# eeprom_emu_bt.net
KiCad netlist of a schematic drawn in EAGLE
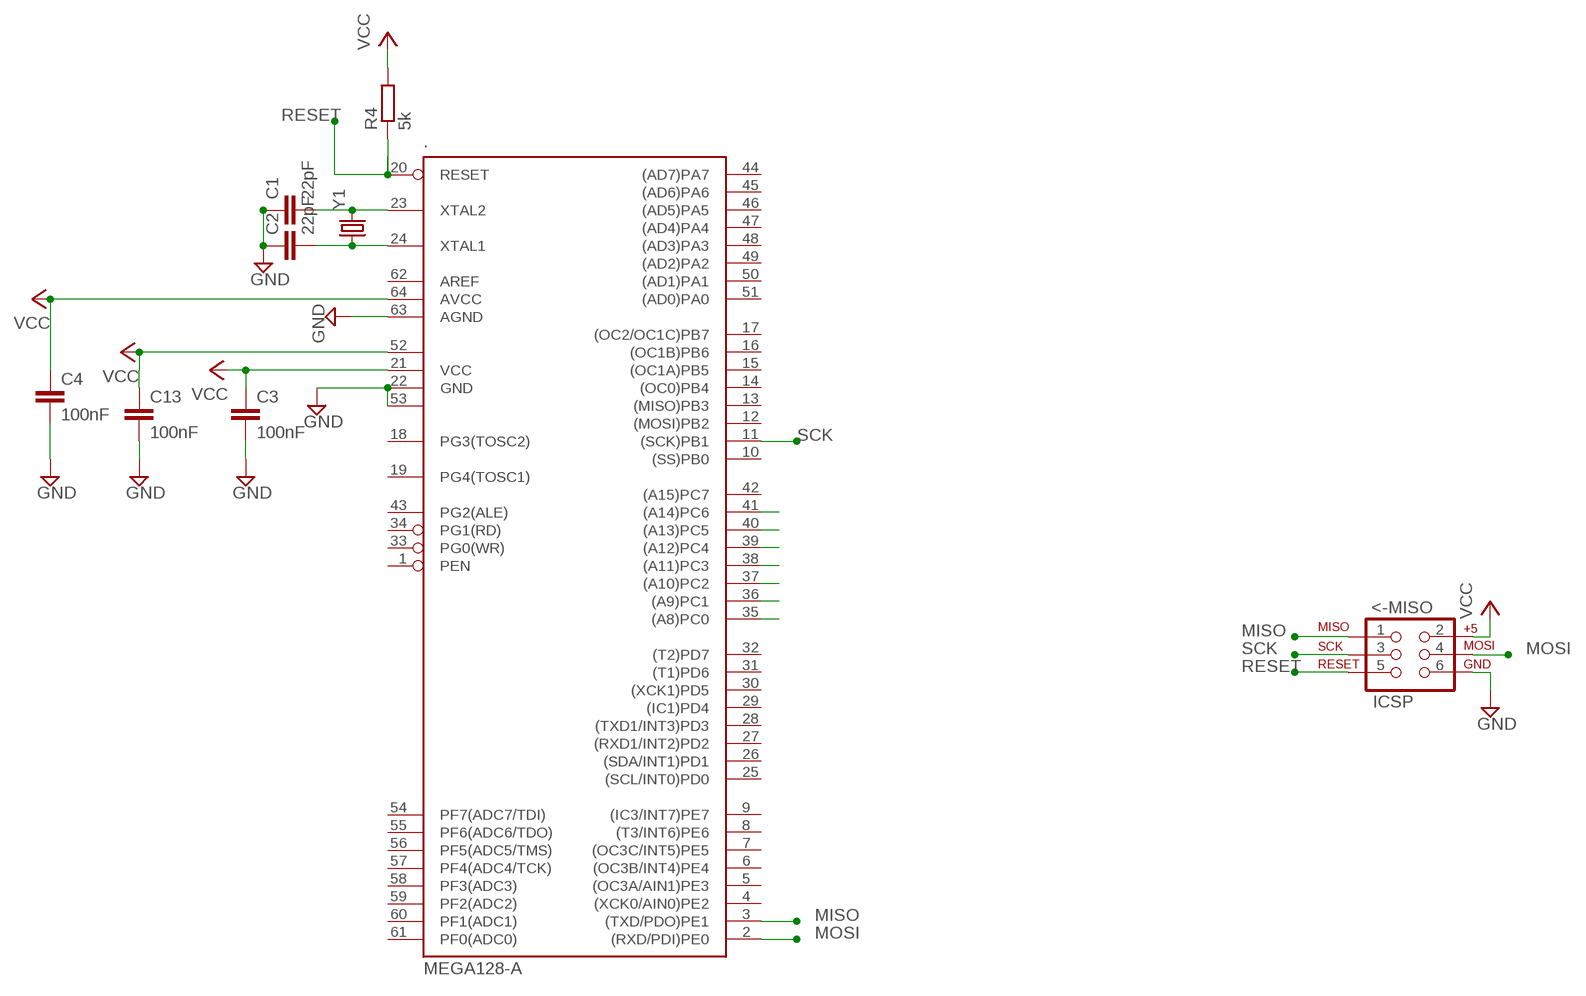
[diagram p0: schematic, sheet 1]

(export (version "E")
  (design (tool "Eeschema 10.0.6"))
  (components
    (comp (ref ".")
      (value "MEGA128-A")
      (footprint "eagle-import:TQFP64")
      (libsource (lib "eagle-import") (part "MEGA128-A"))
    )
    (comp (ref "<-MISO")
      (value "ICSP")
      (footprint "eagle-import:2X3")
      (libsource (lib "eagle-import") (part "AVR_SPI_PRG_6PTH"))
    )
    (comp (ref "C1")
      (value "22pF")
      (footprint "eagle-import:C0805")
      (libsource (lib "eagle-import") (part "C-EUC0805"))
    )
    (comp (ref "C2")
      (value "22pF")
      (footprint "eagle-import:C0805")
      (libsource (lib "eagle-import") (part "C-EUC0805"))
    )
    (comp (ref "C3")
      (value "100nF")
      (footprint "eagle-import:C0805")
      (libsource (lib "eagle-import") (part "C-EUC0805"))
    )
    (comp (ref "C4")
      (value "100nF")
      (footprint "eagle-import:C0805")
      (libsource (lib "eagle-import") (part "C-EUC0805"))
    )
    (comp (ref "C13")
      (value "100nF")
      (footprint "eagle-import:C0805")
      (libsource (lib "eagle-import") (part "C-EUC0805"))
    )
    (comp (ref "R4")
      (value "5k")
      (footprint "eagle-import:R0805")
      (libsource (lib "eagle-import") (part "R-EU_R0805"))
    )
    (comp (ref "Y1")
      (value "CRYSTALHC49US")
      (footprint "eagle-import:HC49US")
      (libsource (lib "eagle-import") (part "CRYSTALHC49US"))
    )
  )
  (nets
    (net (code "1") (name "/MISO") (class "Default")
      (node (ref ".") (pin "3") (pinfunction "(TXD/PDO)PE1_3") (pintype "bidirectional"))
      (node (ref "<-MISO") (pin "1") (pinfunction "1_1") (pintype "passive"))
    )
    (net (code "2") (name "/MOSI") (class "Default")
      (node (ref ".") (pin "2") (pinfunction "(RXD/PDI)PE0_2") (pintype "bidirectional"))
      (node (ref "<-MISO") (pin "4") (pinfunction "4_4") (pintype "passive"))
    )
    (net (code "3") (name "/RESET") (class "Default")
      (node (ref ".") (pin "20") (pinfunction "RESET_20") (pintype "input"))
      (node (ref "<-MISO") (pin "5") (pinfunction "5_5") (pintype "passive"))
      (node (ref "R4") (pin "1") (pinfunction "1_1") (pintype "passive"))
    )
    (net (code "4") (name "/SCK") (class "Default")
      (node (ref ".") (pin "11") (pinfunction "(SCK)PB1_11") (pintype "bidirectional"))
      (node (ref "<-MISO") (pin "3") (pinfunction "3_3") (pintype "passive"))
    )
    (net (code "5") (name "GND") (class "Default")
      (node (ref ".") (pin "22") (pinfunction "GND_22") (pintype "power_in"))
      (node (ref ".") (pin "53") (pinfunction "GND1_53") (pintype "power_in"))
      (node (ref ".") (pin "63") (pinfunction "AGND_63") (pintype "bidirectional"))
      (node (ref "<-MISO") (pin "6") (pinfunction "6_6") (pintype "passive"))
      (node (ref "C1") (pin "1") (pinfunction "1_1") (pintype "passive"))
      (node (ref "C13") (pin "2") (pinfunction "2_2") (pintype "passive"))
      (node (ref "C2") (pin "1") (pinfunction "1_1") (pintype "passive"))
      (node (ref "C3") (pin "2") (pinfunction "2_2") (pintype "passive"))
      (node (ref "C4") (pin "2") (pinfunction "2_2") (pintype "passive"))
    )
    (net (code "6") (name "Net-(.-XTAL1)") (class "Default")
      (node (ref ".") (pin "24") (pinfunction "XTAL1_24") (pintype "bidirectional"))
      (node (ref "C2") (pin "2") (pinfunction "2_2") (pintype "passive"))
      (node (ref "Y1") (pin "1") (pinfunction "1_1") (pintype "passive"))
    )
    (net (code "7") (name "Net-(.-XTAL2)") (class "Default")
      (node (ref ".") (pin "23") (pinfunction "XTAL2_23") (pintype "bidirectional"))
      (node (ref "C1") (pin "2") (pinfunction "2_2") (pintype "passive"))
      (node (ref "Y1") (pin "2") (pinfunction "2_2") (pintype "passive"))
    )
    (net (code "8") (name "VCC") (class "Default")
      (node (ref ".") (pin "21") (pinfunction "VCC_21") (pintype "power_in"))
      (node (ref ".") (pin "52") (pinfunction "VCC1_52") (pintype "power_in"))
      (node (ref ".") (pin "64") (pinfunction "AVCC_64") (pintype "bidirectional"))
      (node (ref "<-MISO") (pin "2") (pinfunction "2_2") (pintype "passive"))
      (node (ref "C13") (pin "1") (pinfunction "1_1") (pintype "passive"))
      (node (ref "C3") (pin "1") (pinfunction "1_1") (pintype "passive"))
      (node (ref "C4") (pin "1") (pinfunction "1_1") (pintype "passive"))
      (node (ref "R4") (pin "2") (pinfunction "2_2") (pintype "passive"))
    )
    (net (code "9") (name "unconnected-(.-(A8)PC0-Pad35)") (class "Default")
      (node (ref ".") (pin "35") (pinfunction "(A8)PC0_35") (pintype "output"))
    )
    (net (code "10") (name "unconnected-(.-(A9)PC1-Pad36)") (class "Default")
      (node (ref ".") (pin "36") (pinfunction "(A9)PC1_36") (pintype "output"))
    )
    (net (code "11") (name "unconnected-(.-(A10)PC2-Pad37)") (class "Default")
      (node (ref ".") (pin "37") (pinfunction "(A10)PC2_37") (pintype "output"))
    )
    (net (code "12") (name "unconnected-(.-(A11)PC3-Pad38)") (class "Default")
      (node (ref ".") (pin "38") (pinfunction "(A11)PC3_38") (pintype "output"))
    )
    (net (code "13") (name "unconnected-(.-(A12)PC4-Pad39)") (class "Default")
      (node (ref ".") (pin "39") (pinfunction "(A12)PC4_39") (pintype "output"))
    )
    (net (code "14") (name "unconnected-(.-(A13)PC5-Pad40)") (class "Default")
      (node (ref ".") (pin "40") (pinfunction "(A13)PC5_40") (pintype "output"))
    )
    (net (code "15") (name "unconnected-(.-(A14)PC6-Pad41)") (class "Default")
      (node (ref ".") (pin "41") (pinfunction "(A14)PC6_41") (pintype "output"))
    )
    (net (code "16") (name "unconnected-(.-(A15)PC7-Pad42)") (class "Default")
      (node (ref ".") (pin "42") (pinfunction "(A15)PC7_42") (pintype "output"))
    )
    (net (code "17") (name "unconnected-(.-(AD0)PA0-Pad51)") (class "Default")
      (node (ref ".") (pin "51") (pinfunction "(AD0)PA0_51") (pintype "bidirectional"))
    )
    (net (code "18") (name "unconnected-(.-(AD1)PA1-Pad50)") (class "Default")
      (node (ref ".") (pin "50") (pinfunction "(AD1)PA1_50") (pintype "bidirectional"))
    )
    (net (code "19") (name "unconnected-(.-(AD2)PA2-Pad49)") (class "Default")
      (node (ref ".") (pin "49") (pinfunction "(AD2)PA2_49") (pintype "bidirectional"))
    )
    (net (code "20") (name "unconnected-(.-(AD3)PA3-Pad48)") (class "Default")
      (node (ref ".") (pin "48") (pinfunction "(AD3)PA3_48") (pintype "bidirectional"))
    )
    (net (code "21") (name "unconnected-(.-(AD4)PA4-Pad47)") (class "Default")
      (node (ref ".") (pin "47") (pinfunction "(AD4)PA4_47") (pintype "bidirectional"))
    )
    (net (code "22") (name "unconnected-(.-(AD5)PA5-Pad46)") (class "Default")
      (node (ref ".") (pin "46") (pinfunction "(AD5)PA5_46") (pintype "bidirectional"))
    )
    (net (code "23") (name "unconnected-(.-(AD6)PA6-Pad45)") (class "Default")
      (node (ref ".") (pin "45") (pinfunction "(AD6)PA6_45") (pintype "bidirectional"))
    )
    (net (code "24") (name "unconnected-(.-(AD7)PA7-Pad44)") (class "Default")
      (node (ref ".") (pin "44") (pinfunction "(AD7)PA7_44") (pintype "bidirectional"))
    )
    (net (code "25") (name "unconnected-(.-(IC1)PD4-Pad29)") (class "Default")
      (node (ref ".") (pin "29") (pinfunction "(IC1)PD4_29") (pintype "bidirectional"))
    )
    (net (code "26") (name "unconnected-(.-(IC3{slash}INT7)PE7-Pad9)") (class "Default")
      (node (ref ".") (pin "9") (pinfunction "(IC3/INT7)PE7_9") (pintype "bidirectional"))
    )
    (net (code "27") (name "unconnected-(.-(MISO)PB3-Pad13)") (class "Default")
      (node (ref ".") (pin "13") (pinfunction "(MISO)PB3_13") (pintype "bidirectional"))
    )
    (net (code "28") (name "unconnected-(.-(MOSI)PB2-Pad12)") (class "Default")
      (node (ref ".") (pin "12") (pinfunction "(MOSI)PB2_12") (pintype "bidirectional"))
    )
    (net (code "29") (name "unconnected-(.-(OC0)PB4-Pad14)") (class "Default")
      (node (ref ".") (pin "14") (pinfunction "(OC0)PB4_14") (pintype "bidirectional"))
    )
    (net (code "30") (name "unconnected-(.-(OC1A)PB5-Pad15)") (class "Default")
      (node (ref ".") (pin "15") (pinfunction "(OC1A)PB5_15") (pintype "bidirectional"))
    )
    (net (code "31") (name "unconnected-(.-(OC1B)PB6-Pad16)") (class "Default")
      (node (ref ".") (pin "16") (pinfunction "(OC1B)PB6_16") (pintype "bidirectional"))
    )
    (net (code "32") (name "unconnected-(.-(OC2{slash}OC1C)PB7-Pad17)") (class "Default")
      (node (ref ".") (pin "17") (pinfunction "(OC2/OC1C)PB7_17") (pintype "bidirectional"))
    )
    (net (code "33") (name "unconnected-(.-(OC3A{slash}AIN1)PE3-Pad5)") (class "Default")
      (node (ref ".") (pin "5") (pinfunction "(OC3A/AIN1)PE3_5") (pintype "bidirectional"))
    )
    (net (code "34") (name "unconnected-(.-(OC3B{slash}INT4)PE4-Pad6)") (class "Default")
      (node (ref ".") (pin "6") (pinfunction "(OC3B/INT4)PE4_6") (pintype "bidirectional"))
    )
    (net (code "35") (name "unconnected-(.-(OC3C{slash}INT5)PE5-Pad7)") (class "Default")
      (node (ref ".") (pin "7") (pinfunction "(OC3C/INT5)PE5_7") (pintype "bidirectional"))
    )
    (net (code "36") (name "unconnected-(.-(RXD1{slash}INT2)PD2-Pad27)") (class "Default")
      (node (ref ".") (pin "27") (pinfunction "(RXD1/INT2)PD2_27") (pintype "bidirectional"))
    )
    (net (code "37") (name "unconnected-(.-(SCL{slash}INT0)PD0-Pad25)") (class "Default")
      (node (ref ".") (pin "25") (pinfunction "(SCL/INT0)PD0_25") (pintype "bidirectional"))
    )
    (net (code "38") (name "unconnected-(.-(SDA{slash}INT1)PD1-Pad26)") (class "Default")
      (node (ref ".") (pin "26") (pinfunction "(SDA/INT1)PD1_26") (pintype "bidirectional"))
    )
    (net (code "39") (name "unconnected-(.-(SS)PB0-Pad10)") (class "Default")
      (node (ref ".") (pin "10") (pinfunction "(SS)PB0_10") (pintype "bidirectional"))
    )
    (net (code "40") (name "unconnected-(.-(T1)PD6-Pad31)") (class "Default")
      (node (ref ".") (pin "31") (pinfunction "(T1)PD6_31") (pintype "bidirectional"))
    )
    (net (code "41") (name "unconnected-(.-(T2)PD7-Pad32)") (class "Default")
      (node (ref ".") (pin "32") (pinfunction "(T2)PD7_32") (pintype "bidirectional"))
    )
    (net (code "42") (name "unconnected-(.-(T3{slash}INT6)PE6-Pad8)") (class "Default")
      (node (ref ".") (pin "8") (pinfunction "(T3/INT6)PE6_8") (pintype "bidirectional"))
    )
    (net (code "43") (name "unconnected-(.-(TXD1{slash}INT3)PD3-Pad28)") (class "Default")
      (node (ref ".") (pin "28") (pinfunction "(TXD1/INT3)PD3_28") (pintype "bidirectional"))
    )
    (net (code "44") (name "unconnected-(.-(XCK0{slash}AIN0)PE2-Pad4)") (class "Default")
      (node (ref ".") (pin "4") (pinfunction "(XCK0/AIN0)PE2_4") (pintype "bidirectional"))
    )
    (net (code "45") (name "unconnected-(.-(XCK1)PD5-Pad30)") (class "Default")
      (node (ref ".") (pin "30") (pinfunction "(XCK1)PD5_30") (pintype "bidirectional"))
    )
    (net (code "46") (name "unconnected-(.-AREF-Pad62)") (class "Default")
      (node (ref ".") (pin "62") (pinfunction "AREF_62") (pintype "bidirectional"))
    )
    (net (code "47") (name "unconnected-(.-PEN-Pad1)") (class "Default")
      (node (ref ".") (pin "1") (pinfunction "PEN_1") (pintype "input"))
    )
    (net (code "48") (name "unconnected-(.-PF0(ADC0)-Pad61)") (class "Default")
      (node (ref ".") (pin "61") (pinfunction "PF0(ADC0)_61") (pintype "input"))
    )
    (net (code "49") (name "unconnected-(.-PF1(ADC1)-Pad60)") (class "Default")
      (node (ref ".") (pin "60") (pinfunction "PF1(ADC1)_60") (pintype "input"))
    )
    (net (code "50") (name "unconnected-(.-PF2(ADC2)-Pad59)") (class "Default")
      (node (ref ".") (pin "59") (pinfunction "PF2(ADC2)_59") (pintype "input"))
    )
    (net (code "51") (name "unconnected-(.-PF3(ADC3)-Pad58)") (class "Default")
      (node (ref ".") (pin "58") (pinfunction "PF3(ADC3)_58") (pintype "input"))
    )
    (net (code "52") (name "unconnected-(.-PF4(ADC4{slash}TCK)-Pad57)") (class "Default")
      (node (ref ".") (pin "57") (pinfunction "PF4(ADC4/TCK)_57") (pintype "input"))
    )
    (net (code "53") (name "unconnected-(.-PF5(ADC5{slash}TMS)-Pad56)") (class "Default")
      (node (ref ".") (pin "56") (pinfunction "PF5(ADC5/TMS)_56") (pintype "input"))
    )
    (net (code "54") (name "unconnected-(.-PF6(ADC6{slash}TDO)-Pad55)") (class "Default")
      (node (ref ".") (pin "55") (pinfunction "PF6(ADC6/TDO)_55") (pintype "input"))
    )
    (net (code "55") (name "unconnected-(.-PF7(ADC7{slash}TDI)-Pad54)") (class "Default")
      (node (ref ".") (pin "54") (pinfunction "PF7(ADC7/TDI)_54") (pintype "input"))
    )
    (net (code "56") (name "unconnected-(.-PG0(WR)-Pad33)") (class "Default")
      (node (ref ".") (pin "33") (pinfunction "PG0(WR)_33") (pintype "bidirectional"))
    )
    (net (code "57") (name "unconnected-(.-PG1(RD)-Pad34)") (class "Default")
      (node (ref ".") (pin "34") (pinfunction "PG1(RD)_34") (pintype "bidirectional"))
    )
    (net (code "58") (name "unconnected-(.-PG2(ALE)-Pad43)") (class "Default")
      (node (ref ".") (pin "43") (pinfunction "PG2(ALE)_43") (pintype "bidirectional"))
    )
    (net (code "59") (name "unconnected-(.-PG3(TOSC2)-Pad18)") (class "Default")
      (node (ref ".") (pin "18") (pinfunction "PG3(TOSC2)_18") (pintype "bidirectional"))
    )
    (net (code "60") (name "unconnected-(.-PG4(TOSC1)-Pad19)") (class "Default")
      (node (ref ".") (pin "19") (pinfunction "PG4(TOSC1)_19") (pintype "bidirectional"))
    )
  )
)
